# signal-board_v1_3.net
KiCad netlist of a schematic drawn in EAGLE
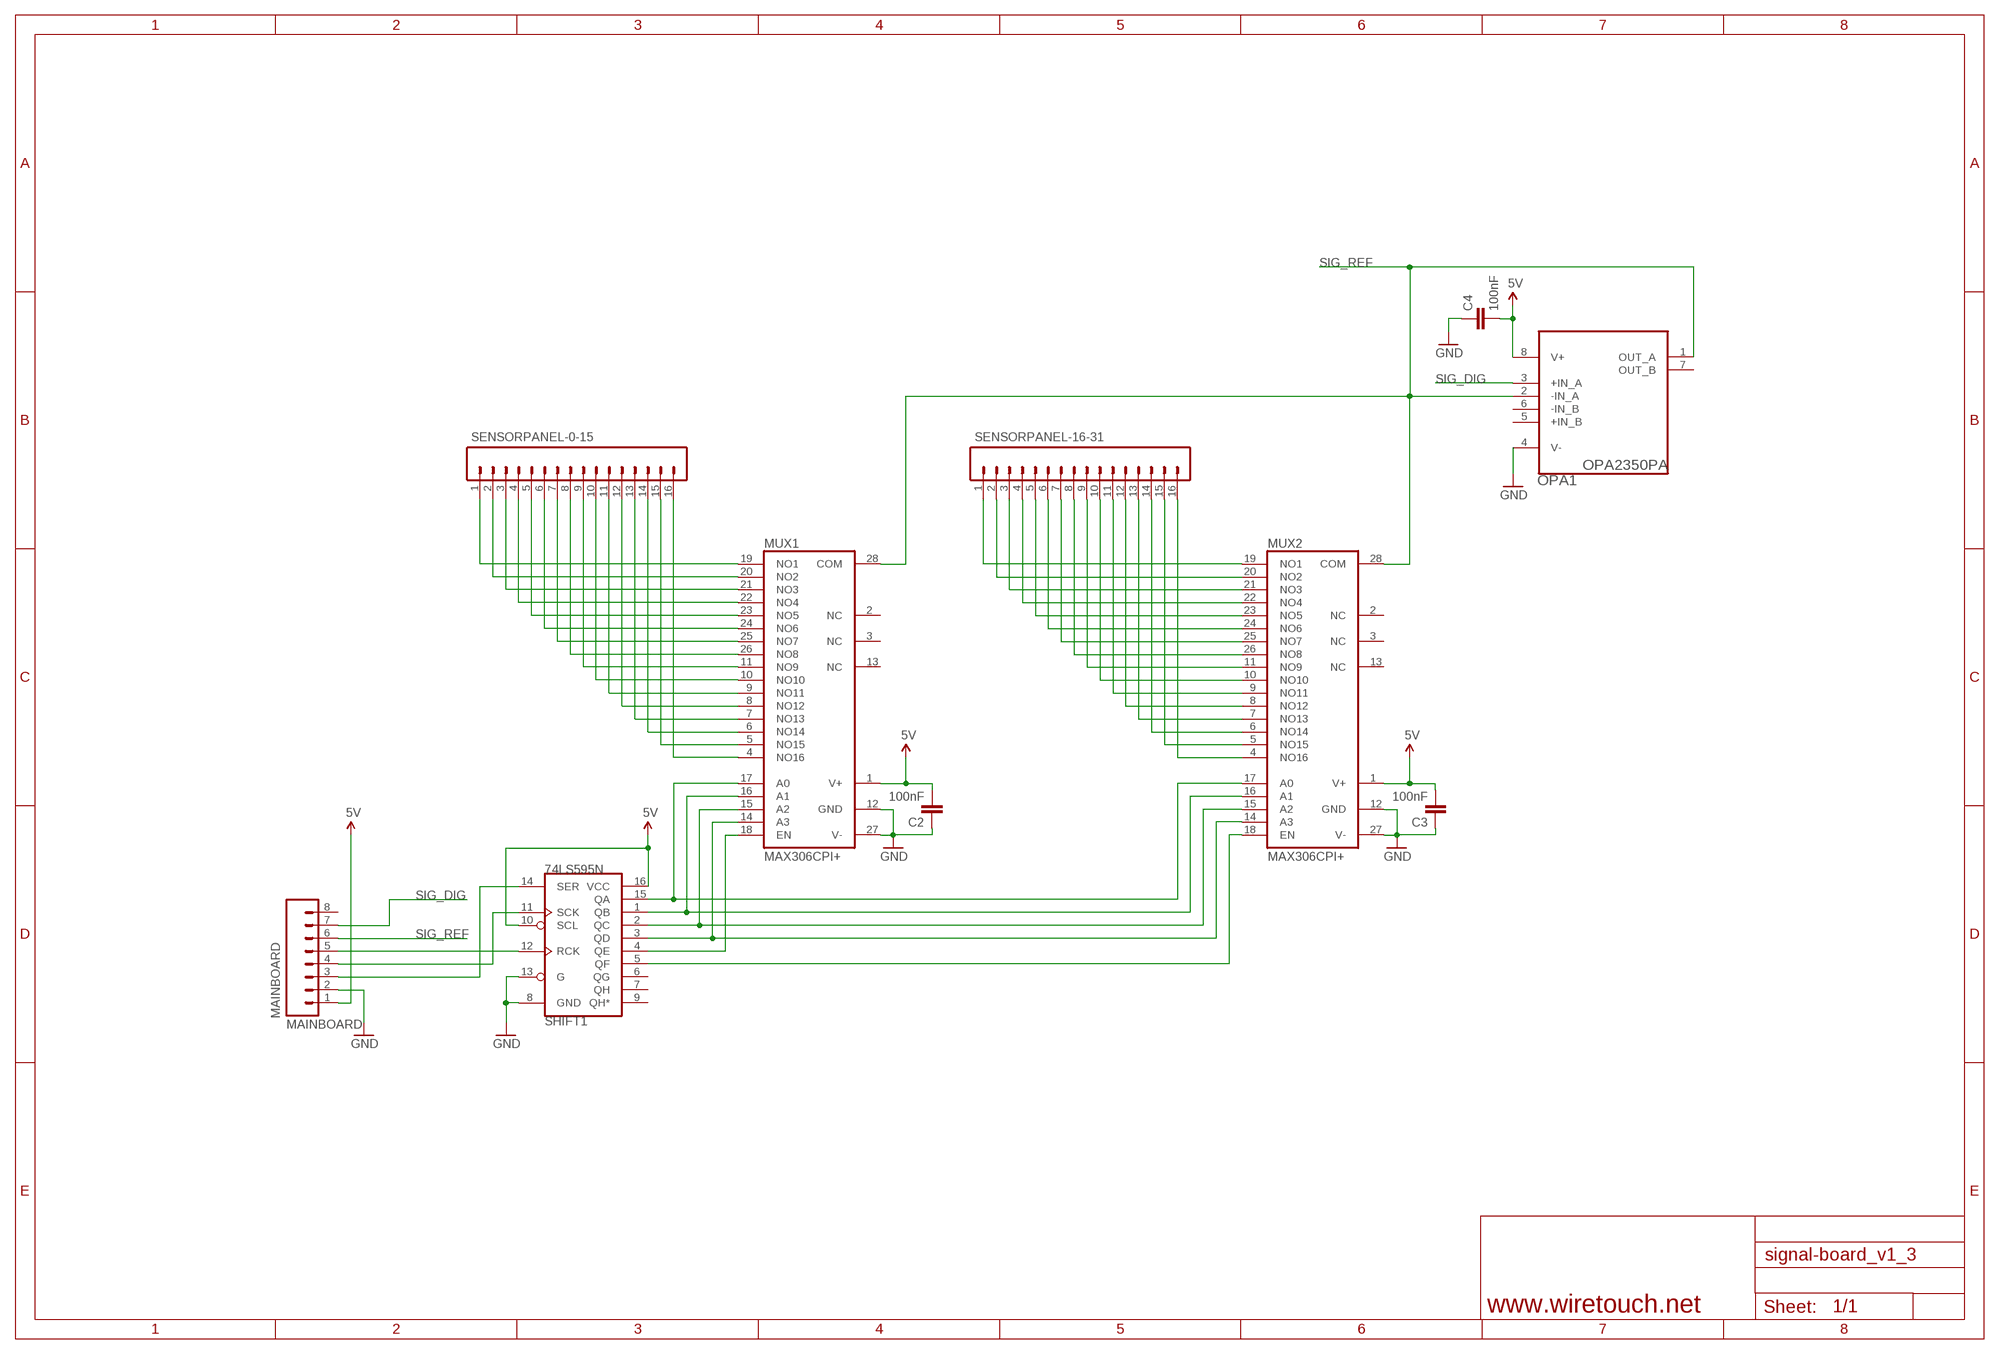
[diagram p0: schematic, sheet 1]

(export (version "E")
  (design (tool "Eeschema 10.0.6"))
  (components
    (comp (ref "C2")
      (value "100nF")
      (footprint "eagle-import:CAP-PTH-SMALL")
      (libsource (lib "eagle-import") (part "CAPPTH"))
    )
    (comp (ref "C3")
      (value "100nF")
      (footprint "eagle-import:CAP-PTH-SMALL")
      (libsource (lib "eagle-import") (part "CAPPTH"))
    )
    (comp (ref "C4")
      (value "100nF")
      (footprint "eagle-import:CAP-PTH-SMALL")
      (libsource (lib "eagle-import") (part "CAPPTH"))
    )
    (comp (ref "MAINBOARD")
      (value "MAINBOARD")
      (footprint "eagle-import:1X08_LONGPADS")
      (libsource (lib "eagle-import") (part "M08LONGPADS"))
    )
    (comp (ref "MUX1")
      (value "MAX306CPI+")
      (footprint "eagle-import:DIL28-6")
      (fields (field (name "MPN") "MAX306CPI"))
      (libsource (lib "eagle-import") (part "MAX306CPI"))
    )
    (comp (ref "MUX2")
      (value "MAX306CPI+")
      (footprint "eagle-import:DIL28-6")
      (fields (field (name "MPN") "MAX306CPI"))
      (libsource (lib "eagle-import") (part "MAX306CPI"))
    )
    (comp (ref "OPA1")
      (value "OPA2350PA")
      (footprint "eagle-import:DIP254P762X508-8")
      (libsource (lib "eagle-import") (part "OPA2350PA"))
    )
    (comp (ref "SENSORPANEL-0-15")
      (value "M16LOCK_LONGPADS")
      (footprint "eagle-import:1X16_LOCK_LONGPADS")
      (libsource (lib "eagle-import") (part "M16LOCK_LONGPADS"))
    )
    (comp (ref "SENSORPANEL-16-31")
      (value "M16LOCK_LONGPADS")
      (footprint "eagle-import:1X16_LOCK_LONGPADS")
      (libsource (lib "eagle-import") (part "M16LOCK_LONGPADS"))
    )
    (comp (ref "SHIFT1")
      (value "74LS595N")
      (footprint "eagle-import:DIL16")
      (libsource (lib "eagle-import") (part "74595NLS"))
    )
  )
  (nets
    (net (code "1") (name "/SIG_DIG") (class "Default")
      (node (ref "MAINBOARD") (pin "7") (pinfunction "7_7") (pintype "passive"))
      (node (ref "OPA1") (pin "3") (pinfunction "+IN_A_3") (pintype "input"))
    )
    (net (code "2") (name "/SIG_REF") (class "Default")
      (node (ref "MAINBOARD") (pin "6") (pinfunction "6_6") (pintype "passive"))
      (node (ref "MUX1") (pin "28") (pinfunction "COM_28") (pintype "passive"))
      (node (ref "MUX2") (pin "28") (pinfunction "COM_28") (pintype "passive"))
      (node (ref "OPA1") (pin "1") (pinfunction "OUT_A_1") (pintype "output"))
      (node (ref "OPA1") (pin "2") (pinfunction "-IN_A_2") (pintype "input"))
    )
    (net (code "3") (name "5V") (class "Default")
      (node (ref "C2") (pin "2") (pinfunction "2_2") (pintype "passive"))
      (node (ref "C3") (pin "2") (pinfunction "2_2") (pintype "passive"))
      (node (ref "C4") (pin "2") (pinfunction "2_2") (pintype "passive"))
      (node (ref "MAINBOARD") (pin "1") (pinfunction "1_1") (pintype "passive"))
      (node (ref "MUX1") (pin "1") (pinfunction "V+_1") (pintype "power_in"))
      (node (ref "MUX2") (pin "1") (pinfunction "V+_1") (pintype "power_in"))
      (node (ref "OPA1") (pin "8") (pinfunction "V+_8") (pintype "power_in"))
      (node (ref "SHIFT1") (pin "10") (pinfunction "SCL_10") (pintype "input"))
      (node (ref "SHIFT1") (pin "16") (pinfunction "VCC_16") (pintype "power_in"))
    )
    (net (code "4") (name "GND") (class "Default")
      (node (ref "C2") (pin "1") (pinfunction "1_1") (pintype "passive"))
      (node (ref "C3") (pin "1") (pinfunction "1_1") (pintype "passive"))
      (node (ref "C4") (pin "1") (pinfunction "1_1") (pintype "passive"))
      (node (ref "MAINBOARD") (pin "2") (pinfunction "2_2") (pintype "passive"))
      (node (ref "MUX1") (pin "12") (pinfunction "GND_12") (pintype "power_in"))
      (node (ref "MUX1") (pin "27") (pinfunction "V-_27") (pintype "power_in"))
      (node (ref "MUX2") (pin "12") (pinfunction "GND_12") (pintype "power_in"))
      (node (ref "MUX2") (pin "27") (pinfunction "V-_27") (pintype "power_in"))
      (node (ref "OPA1") (pin "4") (pinfunction "V-_4") (pintype "power_in"))
      (node (ref "SHIFT1") (pin "13") (pinfunction "G_13") (pintype "input"))
      (node (ref "SHIFT1") (pin "8") (pinfunction "GND_8") (pintype "power_in"))
    )
    (net (code "5") (name "Net-(MUX1-A0)") (class "Default")
      (node (ref "MUX1") (pin "17") (pinfunction "A0_17") (pintype "input"))
      (node (ref "MUX2") (pin "17") (pinfunction "A0_17") (pintype "input"))
      (node (ref "SHIFT1") (pin "15") (pinfunction "QA_15") (pintype "tri_state"))
    )
    (net (code "6") (name "Net-(MUX1-A1)") (class "Default")
      (node (ref "MUX1") (pin "16") (pinfunction "A1_16") (pintype "input"))
      (node (ref "MUX2") (pin "16") (pinfunction "A1_16") (pintype "input"))
      (node (ref "SHIFT1") (pin "1") (pinfunction "QB_1") (pintype "tri_state"))
    )
    (net (code "7") (name "Net-(MUX1-A2)") (class "Default")
      (node (ref "MUX1") (pin "15") (pinfunction "A2_15") (pintype "input"))
      (node (ref "MUX2") (pin "15") (pinfunction "A2_15") (pintype "input"))
      (node (ref "SHIFT1") (pin "2") (pinfunction "QC_2") (pintype "tri_state"))
    )
    (net (code "8") (name "Net-(MUX1-A3)") (class "Default")
      (node (ref "MUX1") (pin "14") (pinfunction "A3_14") (pintype "input"))
      (node (ref "MUX2") (pin "14") (pinfunction "A3_14") (pintype "input"))
      (node (ref "SHIFT1") (pin "3") (pinfunction "QD_3") (pintype "tri_state"))
    )
    (net (code "9") (name "Net-(MUX1-EN)") (class "Default")
      (node (ref "MUX1") (pin "18") (pinfunction "EN_18") (pintype "input"))
      (node (ref "SHIFT1") (pin "4") (pinfunction "QE_4") (pintype "tri_state"))
    )
    (net (code "10") (name "Net-(MUX1-NO1)") (class "Default")
      (node (ref "MUX1") (pin "19") (pinfunction "NO1_19") (pintype "passive"))
      (node (ref "SENSORPANEL-0-15") (pin "1") (pinfunction "1_1") (pintype "passive"))
    )
    (net (code "11") (name "Net-(MUX1-NO2)") (class "Default")
      (node (ref "MUX1") (pin "20") (pinfunction "NO2_20") (pintype "passive"))
      (node (ref "SENSORPANEL-0-15") (pin "2") (pinfunction "2_2") (pintype "passive"))
    )
    (net (code "12") (name "Net-(MUX1-NO3)") (class "Default")
      (node (ref "MUX1") (pin "21") (pinfunction "NO3_21") (pintype "passive"))
      (node (ref "SENSORPANEL-0-15") (pin "3") (pinfunction "3_3") (pintype "passive"))
    )
    (net (code "13") (name "Net-(MUX1-NO4)") (class "Default")
      (node (ref "MUX1") (pin "22") (pinfunction "NO4_22") (pintype "passive"))
      (node (ref "SENSORPANEL-0-15") (pin "4") (pinfunction "4_4") (pintype "passive"))
    )
    (net (code "14") (name "Net-(MUX1-NO5)") (class "Default")
      (node (ref "MUX1") (pin "23") (pinfunction "NO5_23") (pintype "passive"))
      (node (ref "SENSORPANEL-0-15") (pin "5") (pinfunction "5_5") (pintype "passive"))
    )
    (net (code "15") (name "Net-(MUX1-NO6)") (class "Default")
      (node (ref "MUX1") (pin "24") (pinfunction "NO6_24") (pintype "passive"))
      (node (ref "SENSORPANEL-0-15") (pin "6") (pinfunction "6_6") (pintype "passive"))
    )
    (net (code "16") (name "Net-(MUX1-NO7)") (class "Default")
      (node (ref "MUX1") (pin "25") (pinfunction "NO7_25") (pintype "passive"))
      (node (ref "SENSORPANEL-0-15") (pin "7") (pinfunction "7_7") (pintype "passive"))
    )
    (net (code "17") (name "Net-(MUX1-NO8)") (class "Default")
      (node (ref "MUX1") (pin "26") (pinfunction "NO8_26") (pintype "passive"))
      (node (ref "SENSORPANEL-0-15") (pin "8") (pinfunction "8_8") (pintype "passive"))
    )
    (net (code "18") (name "Net-(MUX1-NO9)") (class "Default")
      (node (ref "MUX1") (pin "11") (pinfunction "NO9_11") (pintype "passive"))
      (node (ref "SENSORPANEL-0-15") (pin "9") (pinfunction "9_9") (pintype "passive"))
    )
    (net (code "19") (name "Net-(MUX1-NO10)") (class "Default")
      (node (ref "MUX1") (pin "10") (pinfunction "NO10_10") (pintype "passive"))
      (node (ref "SENSORPANEL-0-15") (pin "10") (pinfunction "10_10") (pintype "passive"))
    )
    (net (code "20") (name "Net-(MUX1-NO11)") (class "Default")
      (node (ref "MUX1") (pin "9") (pinfunction "NO11_9") (pintype "passive"))
      (node (ref "SENSORPANEL-0-15") (pin "11") (pinfunction "11_11") (pintype "passive"))
    )
    (net (code "21") (name "Net-(MUX1-NO12)") (class "Default")
      (node (ref "MUX1") (pin "8") (pinfunction "NO12_8") (pintype "passive"))
      (node (ref "SENSORPANEL-0-15") (pin "12") (pinfunction "12_12") (pintype "passive"))
    )
    (net (code "22") (name "Net-(MUX1-NO13)") (class "Default")
      (node (ref "MUX1") (pin "7") (pinfunction "NO13_7") (pintype "passive"))
      (node (ref "SENSORPANEL-0-15") (pin "13") (pinfunction "13_13") (pintype "passive"))
    )
    (net (code "23") (name "Net-(MUX1-NO14)") (class "Default")
      (node (ref "MUX1") (pin "6") (pinfunction "NO14_6") (pintype "passive"))
      (node (ref "SENSORPANEL-0-15") (pin "14") (pinfunction "14_14") (pintype "passive"))
    )
    (net (code "24") (name "Net-(MUX1-NO15)") (class "Default")
      (node (ref "MUX1") (pin "5") (pinfunction "NO15_5") (pintype "passive"))
      (node (ref "SENSORPANEL-0-15") (pin "15") (pinfunction "15_15") (pintype "passive"))
    )
    (net (code "25") (name "Net-(MUX1-NO16)") (class "Default")
      (node (ref "MUX1") (pin "4") (pinfunction "NO16_4") (pintype "passive"))
      (node (ref "SENSORPANEL-0-15") (pin "16") (pinfunction "16_16") (pintype "passive"))
    )
    (net (code "26") (name "Net-(MUX2-EN)") (class "Default")
      (node (ref "MUX2") (pin "18") (pinfunction "EN_18") (pintype "input"))
      (node (ref "SHIFT1") (pin "5") (pinfunction "QF_5") (pintype "tri_state"))
    )
    (net (code "27") (name "Net-(MUX2-NO1)") (class "Default")
      (node (ref "MUX2") (pin "19") (pinfunction "NO1_19") (pintype "passive"))
      (node (ref "SENSORPANEL-16-31") (pin "1") (pinfunction "1_1") (pintype "passive"))
    )
    (net (code "28") (name "Net-(MUX2-NO2)") (class "Default")
      (node (ref "MUX2") (pin "20") (pinfunction "NO2_20") (pintype "passive"))
      (node (ref "SENSORPANEL-16-31") (pin "2") (pinfunction "2_2") (pintype "passive"))
    )
    (net (code "29") (name "Net-(MUX2-NO3)") (class "Default")
      (node (ref "MUX2") (pin "21") (pinfunction "NO3_21") (pintype "passive"))
      (node (ref "SENSORPANEL-16-31") (pin "3") (pinfunction "3_3") (pintype "passive"))
    )
    (net (code "30") (name "Net-(MUX2-NO4)") (class "Default")
      (node (ref "MUX2") (pin "22") (pinfunction "NO4_22") (pintype "passive"))
      (node (ref "SENSORPANEL-16-31") (pin "4") (pinfunction "4_4") (pintype "passive"))
    )
    (net (code "31") (name "Net-(MUX2-NO5)") (class "Default")
      (node (ref "MUX2") (pin "23") (pinfunction "NO5_23") (pintype "passive"))
      (node (ref "SENSORPANEL-16-31") (pin "5") (pinfunction "5_5") (pintype "passive"))
    )
    (net (code "32") (name "Net-(MUX2-NO6)") (class "Default")
      (node (ref "MUX2") (pin "24") (pinfunction "NO6_24") (pintype "passive"))
      (node (ref "SENSORPANEL-16-31") (pin "6") (pinfunction "6_6") (pintype "passive"))
    )
    (net (code "33") (name "Net-(MUX2-NO7)") (class "Default")
      (node (ref "MUX2") (pin "25") (pinfunction "NO7_25") (pintype "passive"))
      (node (ref "SENSORPANEL-16-31") (pin "7") (pinfunction "7_7") (pintype "passive"))
    )
    (net (code "34") (name "Net-(MUX2-NO8)") (class "Default")
      (node (ref "MUX2") (pin "26") (pinfunction "NO8_26") (pintype "passive"))
      (node (ref "SENSORPANEL-16-31") (pin "8") (pinfunction "8_8") (pintype "passive"))
    )
    (net (code "35") (name "Net-(MUX2-NO9)") (class "Default")
      (node (ref "MUX2") (pin "11") (pinfunction "NO9_11") (pintype "passive"))
      (node (ref "SENSORPANEL-16-31") (pin "9") (pinfunction "9_9") (pintype "passive"))
    )
    (net (code "36") (name "Net-(MUX2-NO10)") (class "Default")
      (node (ref "MUX2") (pin "10") (pinfunction "NO10_10") (pintype "passive"))
      (node (ref "SENSORPANEL-16-31") (pin "10") (pinfunction "10_10") (pintype "passive"))
    )
    (net (code "37") (name "Net-(MUX2-NO11)") (class "Default")
      (node (ref "MUX2") (pin "9") (pinfunction "NO11_9") (pintype "passive"))
      (node (ref "SENSORPANEL-16-31") (pin "11") (pinfunction "11_11") (pintype "passive"))
    )
    (net (code "38") (name "Net-(MUX2-NO12)") (class "Default")
      (node (ref "MUX2") (pin "8") (pinfunction "NO12_8") (pintype "passive"))
      (node (ref "SENSORPANEL-16-31") (pin "12") (pinfunction "12_12") (pintype "passive"))
    )
    (net (code "39") (name "Net-(MUX2-NO13)") (class "Default")
      (node (ref "MUX2") (pin "7") (pinfunction "NO13_7") (pintype "passive"))
      (node (ref "SENSORPANEL-16-31") (pin "13") (pinfunction "13_13") (pintype "passive"))
    )
    (net (code "40") (name "Net-(MUX2-NO14)") (class "Default")
      (node (ref "MUX2") (pin "6") (pinfunction "NO14_6") (pintype "passive"))
      (node (ref "SENSORPANEL-16-31") (pin "14") (pinfunction "14_14") (pintype "passive"))
    )
    (net (code "41") (name "Net-(MUX2-NO15)") (class "Default")
      (node (ref "MUX2") (pin "5") (pinfunction "NO15_5") (pintype "passive"))
      (node (ref "SENSORPANEL-16-31") (pin "15") (pinfunction "15_15") (pintype "passive"))
    )
    (net (code "42") (name "Net-(MUX2-NO16)") (class "Default")
      (node (ref "MUX2") (pin "4") (pinfunction "NO16_4") (pintype "passive"))
      (node (ref "SENSORPANEL-16-31") (pin "16") (pinfunction "16_16") (pintype "passive"))
    )
    (net (code "43") (name "Net-(SHIFT1-RCK)") (class "Default")
      (node (ref "MAINBOARD") (pin "5") (pinfunction "5_5") (pintype "passive"))
      (node (ref "SHIFT1") (pin "12") (pinfunction "RCK_12") (pintype "input"))
    )
    (net (code "44") (name "Net-(SHIFT1-SCK)") (class "Default")
      (node (ref "MAINBOARD") (pin "4") (pinfunction "4_4") (pintype "passive"))
      (node (ref "SHIFT1") (pin "11") (pinfunction "SCK_11") (pintype "input"))
    )
    (net (code "45") (name "Net-(SHIFT1-SER)") (class "Default")
      (node (ref "MAINBOARD") (pin "3") (pinfunction "3_3") (pintype "passive"))
      (node (ref "SHIFT1") (pin "14") (pinfunction "SER_14") (pintype "input"))
    )
    (net (code "46") (name "unconnected-(MAINBOARD-Pad8)") (class "Default")
      (node (ref "MAINBOARD") (pin "8") (pinfunction "8_8") (pintype "passive"))
    )
    (net (code "47") (name "unconnected-(MUX1-NC-Pad2)") (class "Default")
      (node (ref "MUX1") (pin "2") (pinfunction "NC_2") (pintype "no_connect"))
    )
    (net (code "48") (name "unconnected-(MUX1-NC-Pad3)") (class "Default")
      (node (ref "MUX1") (pin "3") (pinfunction "NC_3") (pintype "no_connect"))
    )
    (net (code "49") (name "unconnected-(MUX1-NC-Pad13)") (class "Default")
      (node (ref "MUX1") (pin "13") (pinfunction "NC_13") (pintype "no_connect"))
    )
    (net (code "50") (name "unconnected-(MUX2-NC-Pad2)") (class "Default")
      (node (ref "MUX2") (pin "2") (pinfunction "NC_2") (pintype "no_connect"))
    )
    (net (code "51") (name "unconnected-(MUX2-NC-Pad3)") (class "Default")
      (node (ref "MUX2") (pin "3") (pinfunction "NC_3") (pintype "no_connect"))
    )
    (net (code "52") (name "unconnected-(MUX2-NC-Pad13)") (class "Default")
      (node (ref "MUX2") (pin "13") (pinfunction "NC_13") (pintype "no_connect"))
    )
    (net (code "53") (name "unconnected-(OPA1-+IN_B-Pad5)") (class "Default")
      (node (ref "OPA1") (pin "5") (pinfunction "+IN_B_5") (pintype "input"))
    )
    (net (code "54") (name "unconnected-(OPA1--IN_B-Pad6)") (class "Default")
      (node (ref "OPA1") (pin "6") (pinfunction "-IN_B_6") (pintype "input"))
    )
    (net (code "55") (name "unconnected-(OPA1-OUT_B-Pad7)") (class "Default")
      (node (ref "OPA1") (pin "7") (pinfunction "OUT_B_7") (pintype "output"))
    )
    (net (code "56") (name "unconnected-(SHIFT1-QG-Pad6)") (class "Default")
      (node (ref "SHIFT1") (pin "6") (pinfunction "QG_6") (pintype "tri_state"))
    )
    (net (code "57") (name "unconnected-(SHIFT1-QH*-Pad9)") (class "Default")
      (node (ref "SHIFT1") (pin "9") (pinfunction "QH*_9") (pintype "tri_state"))
    )
    (net (code "58") (name "unconnected-(SHIFT1-QH-Pad7)") (class "Default")
      (node (ref "SHIFT1") (pin "7") (pinfunction "QH_7") (pintype "tri_state"))
    )
  )
)
